# Speed_Control_Relays.net
KiCad netlist of a schematic drawn in EAGLE
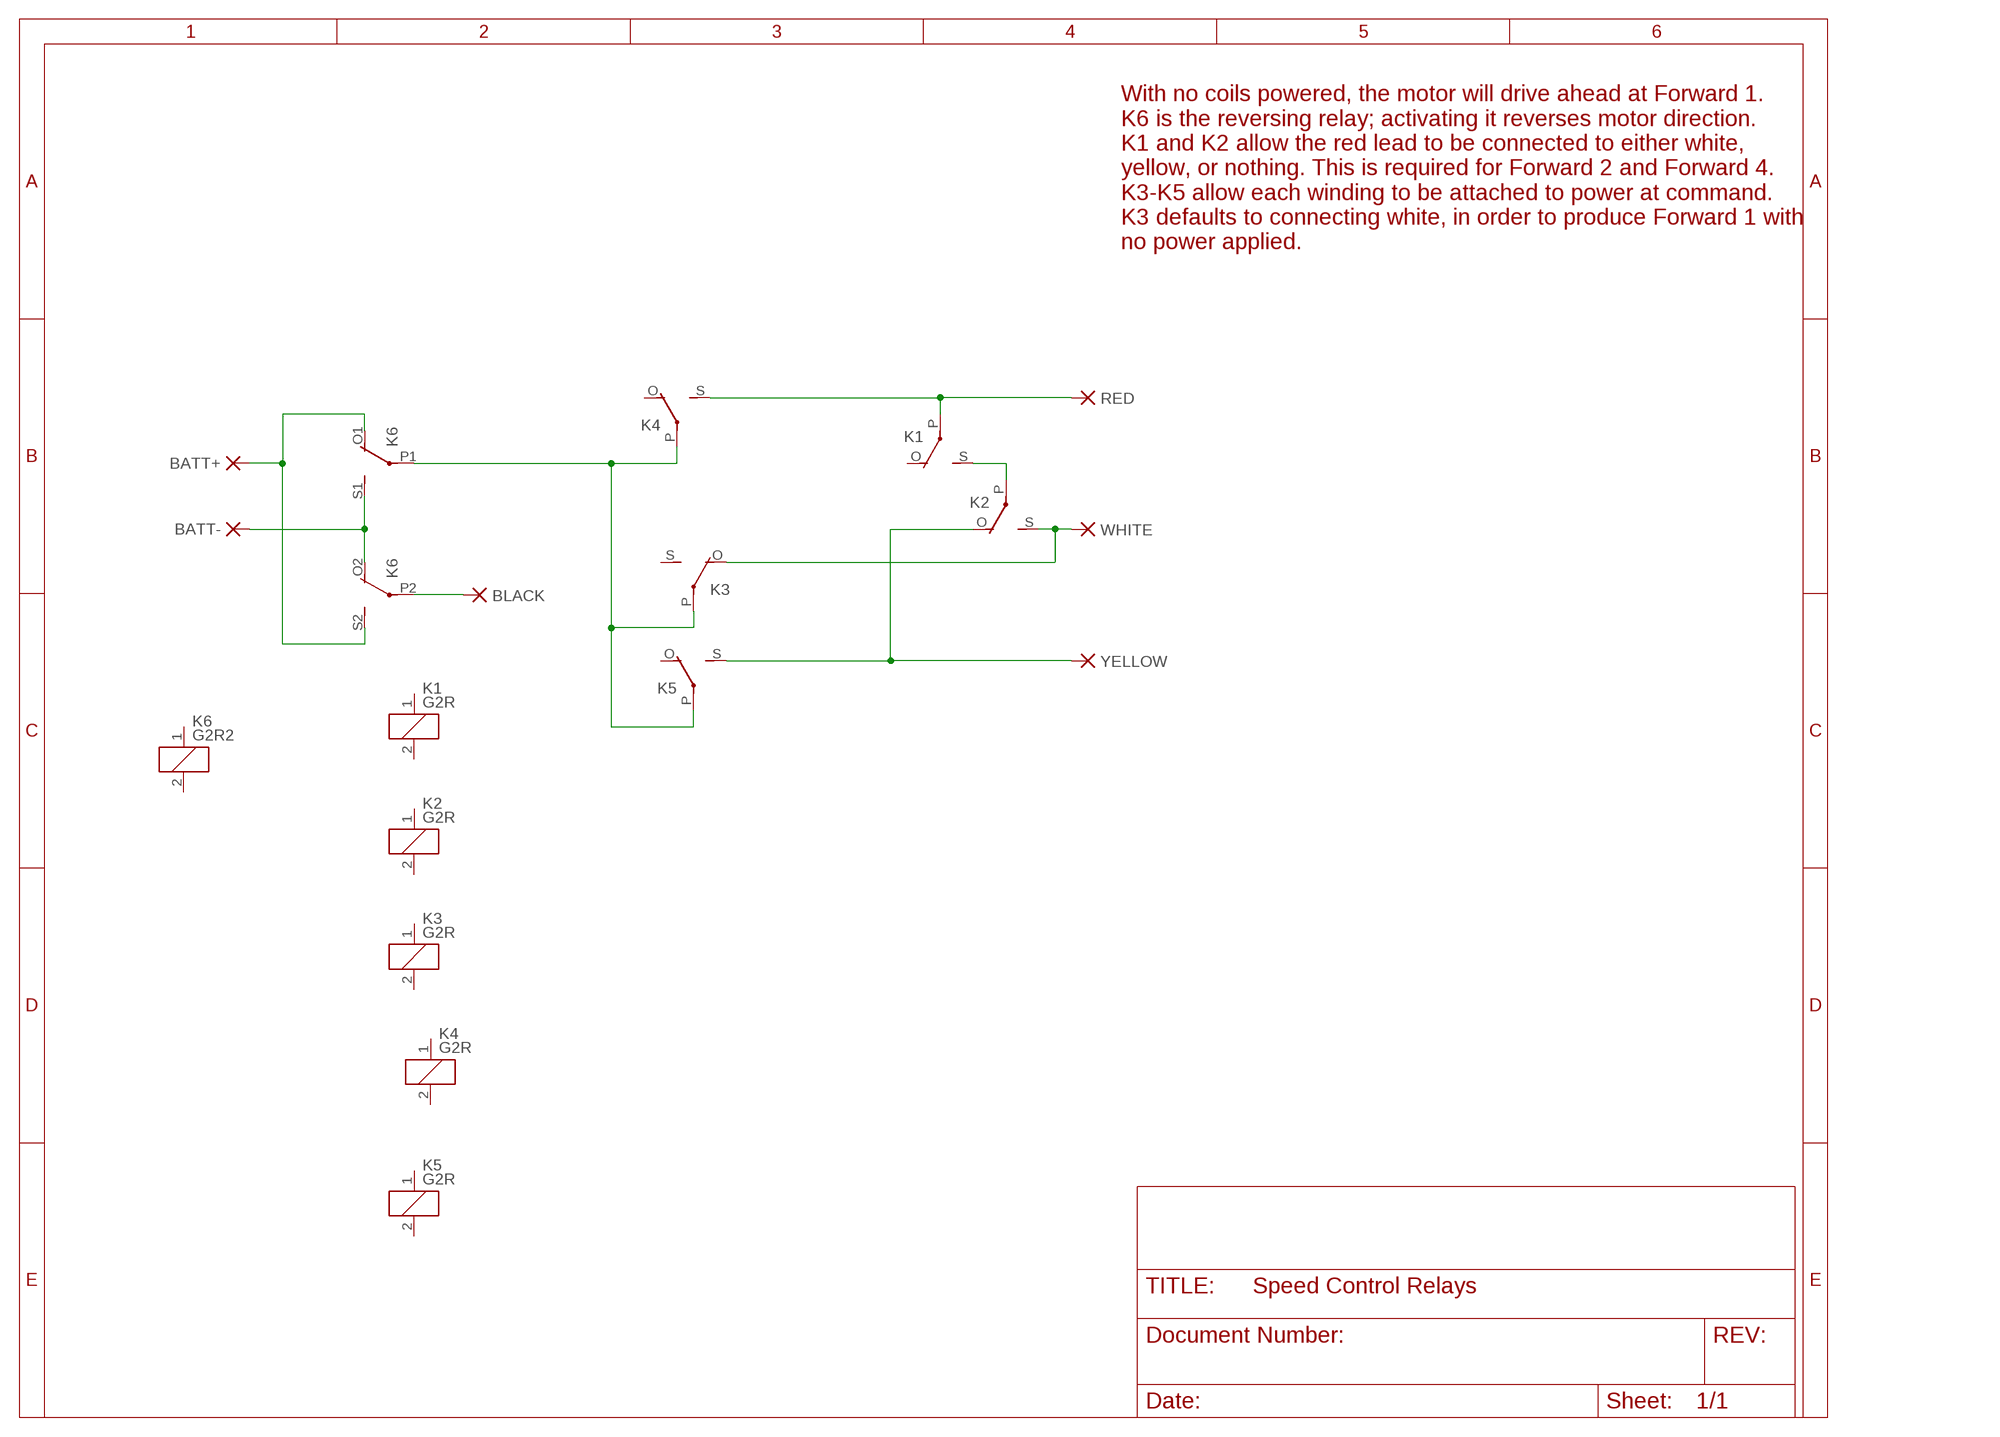
[diagram p0: schematic, sheet 1]

(export (version "E")
  (design (tool "Eeschema 10.0.6"))
  (components
    (comp (ref "BATT+")
      (value "PAD-0240")
      (footprint "eagle-import:0240")
      (libsource (lib "eagle-import") (part "PAD-0240"))
    )
    (comp (ref "BATT-")
      (value "PAD-0240")
      (footprint "eagle-import:0240")
      (libsource (lib "eagle-import") (part "PAD-0240"))
    )
    (comp (ref "BLACK")
      (value "PAD-0240")
      (footprint "eagle-import:0240")
      (libsource (lib "eagle-import") (part "PAD-0240"))
    )
    (comp (ref "K1")
      (value "G2R")
      (footprint "eagle-import:G2R")
      (libsource (lib "eagle-import") (part "G2R"))
    )
    (comp (ref "K2")
      (value "G2R")
      (footprint "eagle-import:G2R")
      (libsource (lib "eagle-import") (part "G2R"))
    )
    (comp (ref "K3")
      (value "G2R")
      (footprint "eagle-import:G2R")
      (libsource (lib "eagle-import") (part "G2R"))
    )
    (comp (ref "K4")
      (value "G2R")
      (footprint "eagle-import:G2R")
      (libsource (lib "eagle-import") (part "G2R"))
    )
    (comp (ref "K5")
      (value "G2R")
      (footprint "eagle-import:G2R")
      (libsource (lib "eagle-import") (part "G2R"))
    )
    (comp (ref "K6")
      (value "G2R2")
      (footprint "eagle-import:G2R2")
      (fields (field (name "MF") "OMRON COMPONENTS USA") (field (name "MPN") "G2R-2-DC6"))
      (libsource (lib "eagle-import") (part "G2R2"))
    )
    (comp (ref "RED")
      (value "PAD-0240")
      (footprint "eagle-import:0240")
      (libsource (lib "eagle-import") (part "PAD-0240"))
    )
    (comp (ref "WHITE")
      (value "PAD-0240")
      (footprint "eagle-import:0240")
      (libsource (lib "eagle-import") (part "PAD-0240"))
    )
    (comp (ref "YELLOW")
      (value "PAD-0240")
      (footprint "eagle-import:0240")
      (libsource (lib "eagle-import") (part "PAD-0240"))
    )
  )
  (nets
    (net (code "1") (name "Net-(BATT+-P)") (class "Default")
      (node (ref "BATT+") (pin "P$1") (pinfunction "P_P$1") (pintype "passive"))
      (node (ref "K6") (pin "O1") (pinfunction "O_O1") (pintype "passive"))
      (node (ref "K6") (pin "S2") (pinfunction "S_S2") (pintype "passive"))
    )
    (net (code "2") (name "Net-(BATT--P)") (class "Default")
      (node (ref "BATT-") (pin "P$1") (pinfunction "P_P$1") (pintype "passive"))
      (node (ref "K6") (pin "O2") (pinfunction "O_O2") (pintype "passive"))
      (node (ref "K6") (pin "S1") (pinfunction "S_S1") (pintype "passive"))
    )
    (net (code "3") (name "Net-(BLACK-P)") (class "Default")
      (node (ref "BLACK") (pin "P$1") (pinfunction "P_P$1") (pintype "passive"))
      (node (ref "K6") (pin "P2") (pinfunction "P_P2") (pintype "passive"))
    )
    (net (code "4") (name "Net-(K1-PadS)") (class "Default")
      (node (ref "K1") (pin "S") (pinfunction "S_S") (pintype "passive"))
      (node (ref "K2") (pin "P") (pinfunction "P_P") (pintype "passive"))
    )
    (net (code "5") (name "Net-(K6B-P)") (class "Default")
      (node (ref "K3") (pin "P") (pinfunction "P_P") (pintype "passive"))
      (node (ref "K4") (pin "P") (pinfunction "P_P") (pintype "passive"))
      (node (ref "K5") (pin "P") (pinfunction "P_P") (pintype "passive"))
      (node (ref "K6") (pin "P1") (pinfunction "P_P1") (pintype "passive"))
    )
    (net (code "6") (name "Net-(RED-P)") (class "Default")
      (node (ref "K1") (pin "P") (pinfunction "P_P") (pintype "passive"))
      (node (ref "K4") (pin "S") (pinfunction "S_S") (pintype "passive"))
      (node (ref "RED") (pin "P$1") (pinfunction "P_P$1") (pintype "passive"))
    )
    (net (code "7") (name "Net-(WHITE-P)") (class "Default")
      (node (ref "K2") (pin "S") (pinfunction "S_S") (pintype "passive"))
      (node (ref "K3") (pin "O") (pinfunction "O_O") (pintype "passive"))
      (node (ref "WHITE") (pin "P$1") (pinfunction "P_P$1") (pintype "passive"))
    )
    (net (code "8") (name "Net-(YELLOW-P)") (class "Default")
      (node (ref "K2") (pin "O") (pinfunction "O_O") (pintype "passive"))
      (node (ref "K5") (pin "S") (pinfunction "S_S") (pintype "passive"))
      (node (ref "YELLOW") (pin "P$1") (pinfunction "P_P$1") (pintype "passive"))
    )
    (net (code "9") (name "unconnected-(K1-Pad1)") (class "Default")
      (node (ref "K1") (pin "1") (pinfunction "1_1") (pintype "passive"))
    )
    (net (code "10") (name "unconnected-(K1-Pad2)") (class "Default")
      (node (ref "K1") (pin "2") (pinfunction "2_2") (pintype "passive"))
    )
    (net (code "11") (name "unconnected-(K1-PadO)") (class "Default")
      (node (ref "K1") (pin "O") (pinfunction "O_O") (pintype "passive"))
    )
    (net (code "12") (name "unconnected-(K2-Pad1)") (class "Default")
      (node (ref "K2") (pin "1") (pinfunction "1_1") (pintype "passive"))
    )
    (net (code "13") (name "unconnected-(K2-Pad2)") (class "Default")
      (node (ref "K2") (pin "2") (pinfunction "2_2") (pintype "passive"))
    )
    (net (code "14") (name "unconnected-(K3-Pad1)") (class "Default")
      (node (ref "K3") (pin "1") (pinfunction "1_1") (pintype "passive"))
    )
    (net (code "15") (name "unconnected-(K3-Pad2)") (class "Default")
      (node (ref "K3") (pin "2") (pinfunction "2_2") (pintype "passive"))
    )
    (net (code "16") (name "unconnected-(K3-PadS)") (class "Default")
      (node (ref "K3") (pin "S") (pinfunction "S_S") (pintype "passive"))
    )
    (net (code "17") (name "unconnected-(K4-Pad1)") (class "Default")
      (node (ref "K4") (pin "1") (pinfunction "1_1") (pintype "passive"))
    )
    (net (code "18") (name "unconnected-(K4-Pad2)") (class "Default")
      (node (ref "K4") (pin "2") (pinfunction "2_2") (pintype "passive"))
    )
    (net (code "19") (name "unconnected-(K4-PadO)") (class "Default")
      (node (ref "K4") (pin "O") (pinfunction "O_O") (pintype "passive"))
    )
    (net (code "20") (name "unconnected-(K5-Pad1)") (class "Default")
      (node (ref "K5") (pin "1") (pinfunction "1_1") (pintype "passive"))
    )
    (net (code "21") (name "unconnected-(K5-Pad2)") (class "Default")
      (node (ref "K5") (pin "2") (pinfunction "2_2") (pintype "passive"))
    )
    (net (code "22") (name "unconnected-(K5-PadO)") (class "Default")
      (node (ref "K5") (pin "O") (pinfunction "O_O") (pintype "passive"))
    )
    (net (code "23") (name "unconnected-(K6-Pad1)") (class "Default")
      (node (ref "K6") (pin "1") (pinfunction "1_1") (pintype "passive"))
    )
    (net (code "24") (name "unconnected-(K6-Pad2)") (class "Default")
      (node (ref "K6") (pin "2") (pinfunction "2_2") (pintype "passive"))
    )
  )
)
